# optical_modul.net
KiCad netlist of a schematic drawn in EAGLE
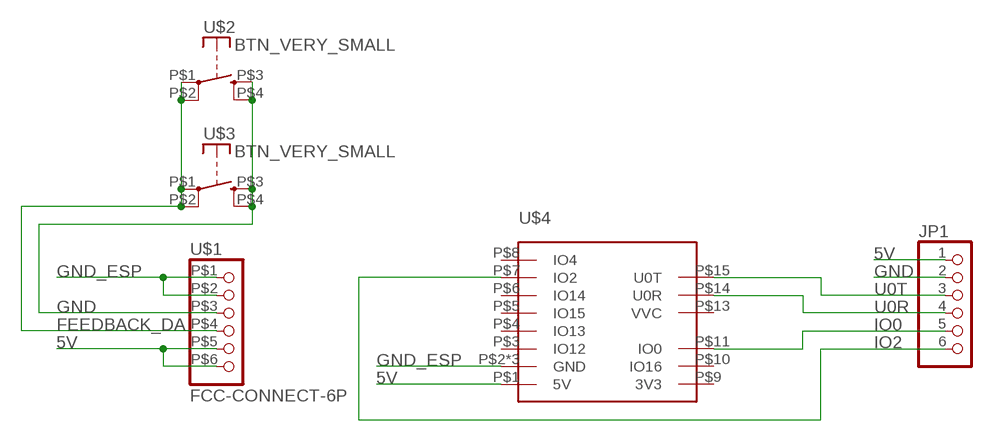
[diagram p0: schematic, sheet 1]

(export (version "E")
  (design (tool "Eeschema 10.0.6"))
  (components
    (comp (ref "JP1")
      (value "PINHD-1X6")
      (footprint "eagle-import:1X06")
      (libsource (lib "eagle-import") (part "PINHD-1X6"))
    )
    (comp (ref "U$1")
      (value "FCC-CONNECT-6P")
      (footprint "eagle-import:FFC-CONNECT-6P-SMD")
      (libsource (lib "eagle-import") (part "FCC-CONNECT-6P"))
    )
    (comp (ref "U$2")
      (value "BTN_VERY_SMALL")
      (footprint "eagle-import:BTN_VERY_SMALL")
      (libsource (lib "eagle-import") (part "BTN_VERY_SMALL"))
    )
    (comp (ref "U$3")
      (value "BTN_VERY_SMALL")
      (footprint "eagle-import:BTN_VERY_SMALL")
      (libsource (lib "eagle-import") (part "BTN_VERY_SMALL"))
    )
    (comp (ref "U$4")
      (value "ESP32-CAM")
      (footprint "eagle-import:ESP32-CAM")
      (libsource (lib "eagle-import") (part "ESP32-CAM"))
    )
  )
  (nets
    (net (code "1") (name "/5V") (class "Default")
      (node (ref "JP1") (pin "1") (pinfunction "1_1") (pintype "passive"))
      (node (ref "U$1") (pin "P$5") (pinfunction "5_P$5") (pintype "passive"))
      (node (ref "U$1") (pin "P$6") (pinfunction "6_P$6") (pintype "passive"))
      (node (ref "U$4") (pin "P$1") (pinfunction "5V_P$1") (pintype "bidirectional"))
    )
    (net (code "2") (name "/FEEDBACK_DA") (class "Default")
      (node (ref "U$1") (pin "P$4") (pinfunction "4_P$4") (pintype "passive"))
      (node (ref "U$2") (pin "P$1") (pinfunction "P_P$1") (pintype "passive"))
      (node (ref "U$2") (pin "P$2") (pinfunction "P_P$2") (pintype "passive"))
      (node (ref "U$3") (pin "P$1") (pinfunction "P_P$1") (pintype "passive"))
      (node (ref "U$3") (pin "P$2") (pinfunction "P_P$2") (pintype "passive"))
    )
    (net (code "3") (name "/GND") (class "Default")
      (node (ref "JP1") (pin "2") (pinfunction "2_2") (pintype "passive"))
      (node (ref "U$1") (pin "P$3") (pinfunction "3_P$3") (pintype "passive"))
      (node (ref "U$2") (pin "P$3") (pinfunction "S_P$3") (pintype "passive"))
      (node (ref "U$2") (pin "P$4") (pinfunction "S_P$4") (pintype "passive"))
      (node (ref "U$3") (pin "P$3") (pinfunction "S_P$3") (pintype "passive"))
      (node (ref "U$3") (pin "P$4") (pinfunction "S_P$4") (pintype "passive"))
    )
    (net (code "4") (name "/GND_ESP") (class "Default")
      (node (ref "U$1") (pin "P$1") (pinfunction "1_P$1") (pintype "passive"))
      (node (ref "U$1") (pin "P$2") (pinfunction "2_P$2") (pintype "passive"))
      (node (ref "U$4") (pin "P$12") (pinfunction "GND_P$12") (pintype "bidirectional"))
      (node (ref "U$4") (pin "P$16") (pinfunction "GND_P$16") (pintype "bidirectional"))
      (node (ref "U$4") (pin "P$2") (pinfunction "GND_P$2") (pintype "bidirectional"))
    )
    (net (code "5") (name "/IO0") (class "Default")
      (node (ref "JP1") (pin "5") (pinfunction "5_5") (pintype "passive"))
      (node (ref "U$4") (pin "P$11") (pinfunction "IO0_P$11") (pintype "bidirectional"))
    )
    (net (code "6") (name "/IO2") (class "Default")
      (node (ref "JP1") (pin "6") (pinfunction "6_6") (pintype "passive"))
      (node (ref "U$4") (pin "P$7") (pinfunction "IO2_P$7") (pintype "bidirectional"))
    )
    (net (code "7") (name "/U0R") (class "Default")
      (node (ref "JP1") (pin "4") (pinfunction "4_4") (pintype "passive"))
      (node (ref "U$4") (pin "P$14") (pinfunction "U0R_P$14") (pintype "bidirectional"))
    )
    (net (code "8") (name "/U0T") (class "Default")
      (node (ref "JP1") (pin "3") (pinfunction "3_3") (pintype "passive"))
      (node (ref "U$4") (pin "P$15") (pinfunction "U0T_P$15") (pintype "bidirectional"))
    )
    (net (code "9") (name "unconnected-(U$4-3V3-PadP$9)") (class "Default")
      (node (ref "U$4") (pin "P$9") (pinfunction "3V3_P$9") (pintype "bidirectional"))
    )
    (net (code "10") (name "unconnected-(U$4-IO4-PadP$8)") (class "Default")
      (node (ref "U$4") (pin "P$8") (pinfunction "IO4_P$8") (pintype "bidirectional"))
    )
    (net (code "11") (name "unconnected-(U$4-IO12-PadP$3)") (class "Default")
      (node (ref "U$4") (pin "P$3") (pinfunction "IO12_P$3") (pintype "bidirectional"))
    )
    (net (code "12") (name "unconnected-(U$4-IO13-PadP$4)") (class "Default")
      (node (ref "U$4") (pin "P$4") (pinfunction "IO13_P$4") (pintype "bidirectional"))
    )
    (net (code "13") (name "unconnected-(U$4-IO14-PadP$6)") (class "Default")
      (node (ref "U$4") (pin "P$6") (pinfunction "IO14_P$6") (pintype "bidirectional"))
    )
    (net (code "14") (name "unconnected-(U$4-IO15-PadP$5)") (class "Default")
      (node (ref "U$4") (pin "P$5") (pinfunction "IO15_P$5") (pintype "bidirectional"))
    )
    (net (code "15") (name "unconnected-(U$4-IO16-PadP$10)") (class "Default")
      (node (ref "U$4") (pin "P$10") (pinfunction "IO16_P$10") (pintype "bidirectional"))
    )
    (net (code "16") (name "unconnected-(U$4-VVC-PadP$13)") (class "Default")
      (node (ref "U$4") (pin "P$13") (pinfunction "VVC_P$13") (pintype "bidirectional"))
    )
  )
)
